# badge.net
KiCad netlist of a schematic drawn in EAGLE
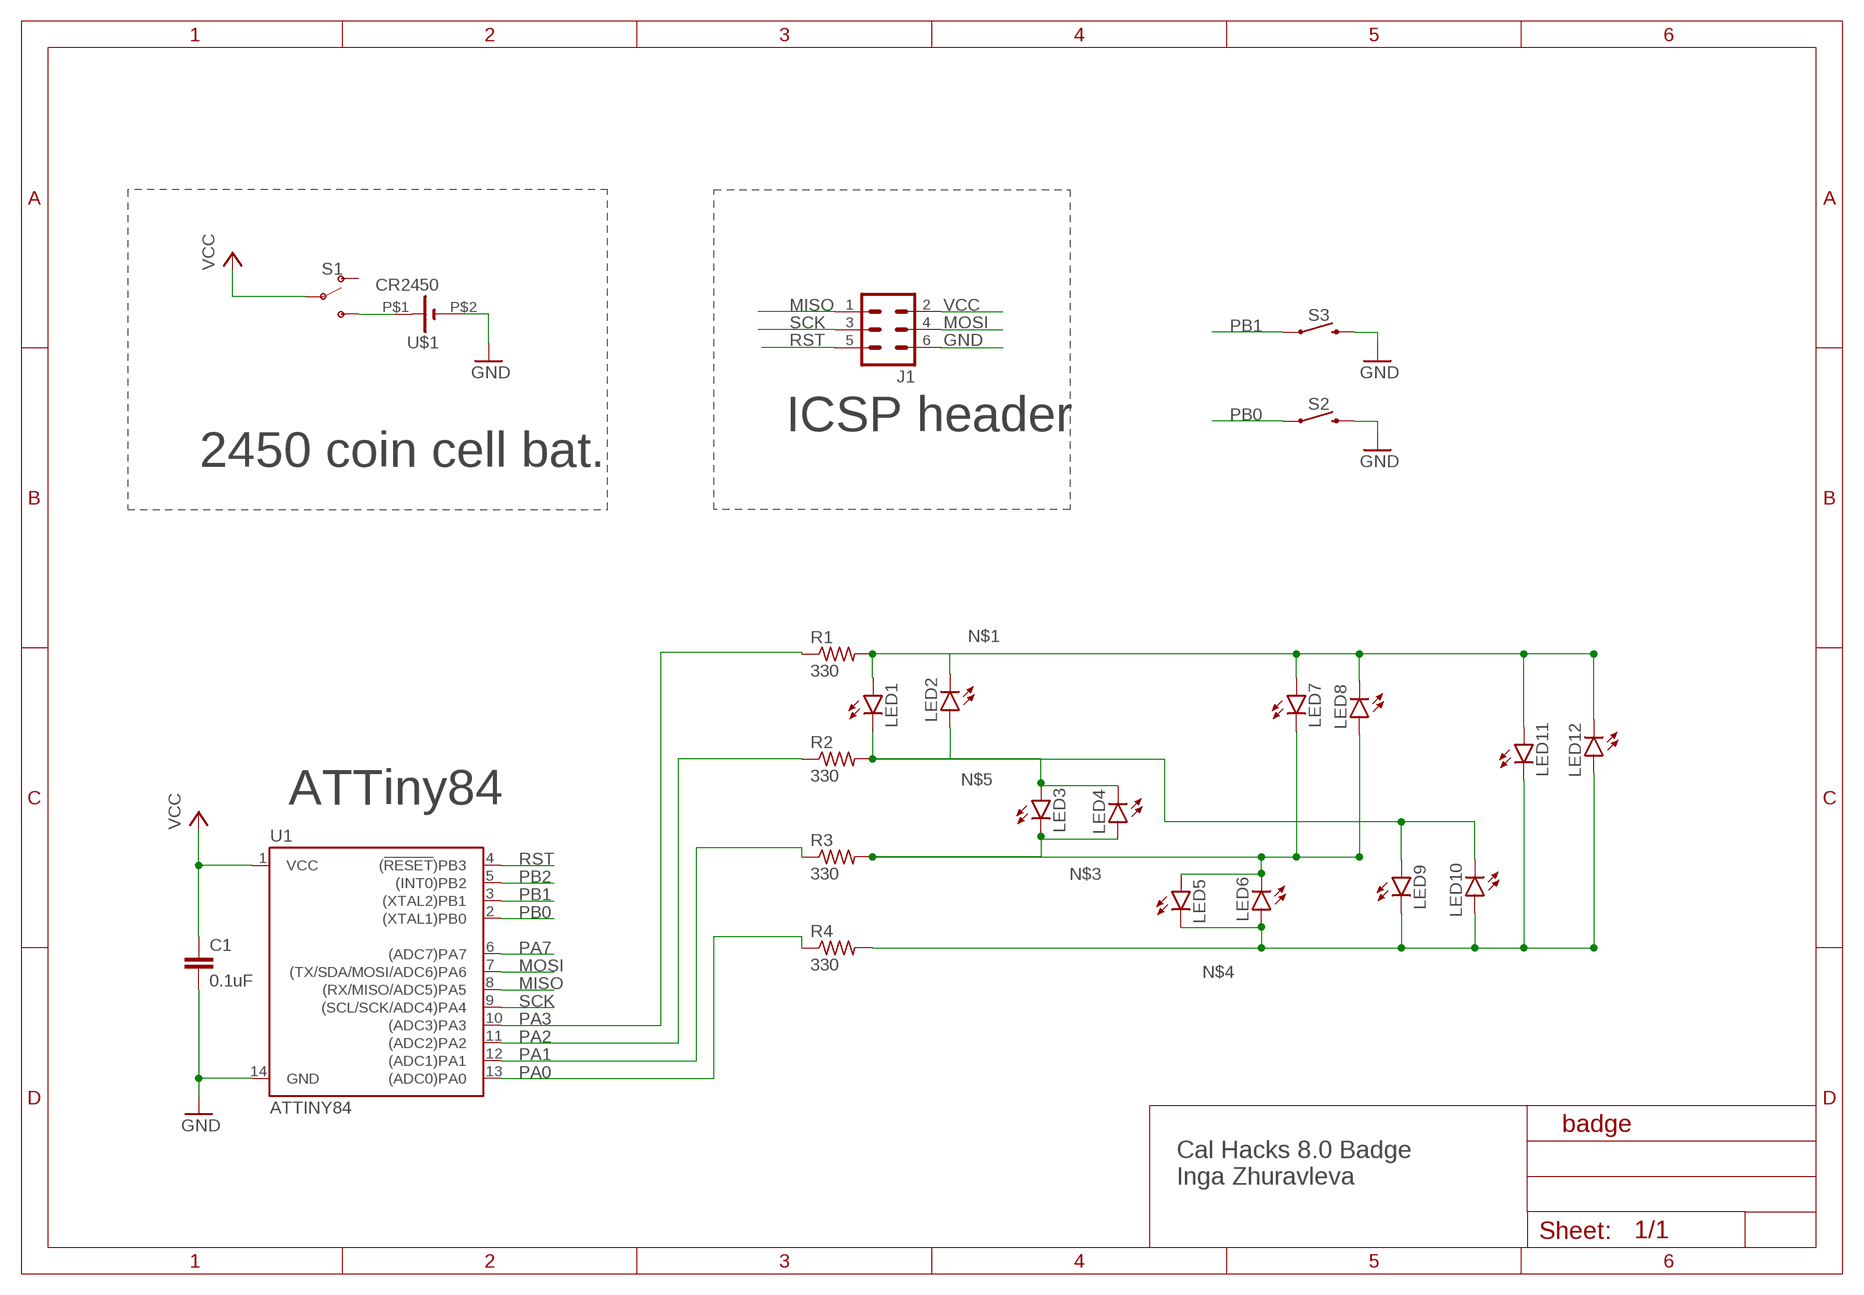
[diagram p0: schematic, sheet 1]

(export (version "E")
  (design (tool "Eeschema 10.0.6"))
  (components
    (comp (ref "C1")
      (value "0.1uF")
      (footprint "eagle-import:C0603")
      (libsource (lib "eagle-import") (part "C-EUC0603"))
    )
    (comp (ref "J1")
      (value "MA03-2")
      (footprint "eagle-import:MA03-2")
      (libsource (lib "eagle-import") (part "MA03-2"))
    )
    (comp (ref "LED1")
      (value "LED3MM")
      (footprint "eagle-import:LED3MM")
      (libsource (lib "eagle-import") (part "LED3MM"))
    )
    (comp (ref "LED2")
      (value "LED3MM")
      (footprint "eagle-import:LED3MM")
      (libsource (lib "eagle-import") (part "LED3MM"))
    )
    (comp (ref "LED3")
      (value "LED3MM")
      (footprint "eagle-import:LED3MM")
      (libsource (lib "eagle-import") (part "LED3MM"))
    )
    (comp (ref "LED4")
      (value "LED3MM")
      (footprint "eagle-import:LED3MM")
      (libsource (lib "eagle-import") (part "LED3MM"))
    )
    (comp (ref "LED5")
      (value "LED3MM")
      (footprint "eagle-import:LED3MM")
      (libsource (lib "eagle-import") (part "LED3MM"))
    )
    (comp (ref "LED6")
      (value "LED3MM")
      (footprint "eagle-import:LED3MM")
      (libsource (lib "eagle-import") (part "LED3MM"))
    )
    (comp (ref "LED7")
      (value "LED3MM")
      (footprint "eagle-import:LED3MM")
      (libsource (lib "eagle-import") (part "LED3MM"))
    )
    (comp (ref "LED8")
      (value "LED3MM")
      (footprint "eagle-import:LED3MM")
      (libsource (lib "eagle-import") (part "LED3MM"))
    )
    (comp (ref "LED9")
      (value "LED3MM")
      (footprint "eagle-import:LED3MM")
      (libsource (lib "eagle-import") (part "LED3MM"))
    )
    (comp (ref "LED10")
      (value "LED3MM")
      (footprint "eagle-import:LED3MM")
      (libsource (lib "eagle-import") (part "LED3MM"))
    )
    (comp (ref "LED11")
      (value "LED3MM")
      (footprint "eagle-import:LED3MM")
      (libsource (lib "eagle-import") (part "LED3MM"))
    )
    (comp (ref "LED12")
      (value "LED3MM")
      (footprint "eagle-import:LED3MM")
      (libsource (lib "eagle-import") (part "LED3MM"))
    )
    (comp (ref "R1")
      (value "330")
      (footprint "eagle-import:R0805")
      (libsource (lib "eagle-import") (part "R-US_R0805"))
    )
    (comp (ref "R2")
      (value "330")
      (footprint "eagle-import:R0805")
      (libsource (lib "eagle-import") (part "R-US_R0805"))
    )
    (comp (ref "R3")
      (value "330")
      (footprint "eagle-import:R0805")
      (libsource (lib "eagle-import") (part "R-US_R0805"))
    )
    (comp (ref "R4")
      (value "330")
      (footprint "eagle-import:R0805")
      (libsource (lib "eagle-import") (part "R-US_R0805"))
    )
    (comp (ref "S1")
      (value "SWITCH-SPDT-PTH-11.6X4.0MM-KIT")
      (footprint "eagle-import:SWITCH_SPDT_PTH_11.6X4.0MM_KIT")
      (libsource (lib "eagle-import") (part "SWITCH-SPDT-PTH-11.6X4.0MM-KIT"))
    )
    (comp (ref "S2")
      (value "MOMENTARY-SWITCH-SPST-SMD-6.2MM-TALL")
      (footprint "eagle-import:TACTILE_SWITCH_SMD_6.2MM_TALL")
      (libsource (lib "eagle-import") (part "MOMENTARY-SWITCH-SPST-SMD-6.2MM-TALL"))
    )
    (comp (ref "S3")
      (value "MOMENTARY-SWITCH-SPST-SMD-6.2MM-TALL")
      (footprint "eagle-import:TACTILE_SWITCH_SMD_6.2MM_TALL")
      (libsource (lib "eagle-import") (part "MOMENTARY-SWITCH-SPST-SMD-6.2MM-TALL"))
    )
    (comp (ref "U$1")
      (value "CR2450")
      (footprint "eagle-import:BAT_2450_XL")
      (fields (field (name "MF") "Murata Electronics"))
      (libsource (lib "eagle-import") (part "CR2450"))
    )
    (comp (ref "U1")
      (value "ATTINY84")
      (footprint "eagle-import:SO14")
      (libsource (lib "eagle-import") (part "ATTINY84"))
    )
  )
  (nets
    (net (code "1") (name "/MISO") (class "Default")
      (node (ref "J1") (pin "1") (pinfunction "1_1") (pintype "passive"))
      (node (ref "U1") (pin "8") (pinfunction "(RX/MISO/ADC5)PA5_8") (pintype "bidirectional"))
    )
    (net (code "2") (name "/MOSI") (class "Default")
      (node (ref "J1") (pin "4") (pinfunction "4_4") (pintype "passive"))
      (node (ref "U1") (pin "7") (pinfunction "(TX/SDA/MOSI/ADC6)PA6_7") (pintype "bidirectional"))
    )
    (net (code "3") (name "/N$1") (class "Default")
      (node (ref "LED1") (pin "A") (pinfunction "A_A") (pintype "passive"))
      (node (ref "LED11") (pin "A") (pinfunction "A_A") (pintype "passive"))
      (node (ref "LED12") (pin "K") (pinfunction "C_K") (pintype "passive"))
      (node (ref "LED2") (pin "K") (pinfunction "C_K") (pintype "passive"))
      (node (ref "LED7") (pin "A") (pinfunction "A_A") (pintype "passive"))
      (node (ref "LED8") (pin "K") (pinfunction "C_K") (pintype "passive"))
      (node (ref "R1") (pin "2") (pinfunction "2_2") (pintype "passive"))
    )
    (net (code "4") (name "/N$3") (class "Default")
      (node (ref "LED3") (pin "K") (pinfunction "C_K") (pintype "passive"))
      (node (ref "LED4") (pin "A") (pinfunction "A_A") (pintype "passive"))
      (node (ref "LED5") (pin "A") (pinfunction "A_A") (pintype "passive"))
      (node (ref "LED6") (pin "K") (pinfunction "C_K") (pintype "passive"))
      (node (ref "LED7") (pin "K") (pinfunction "C_K") (pintype "passive"))
      (node (ref "LED8") (pin "A") (pinfunction "A_A") (pintype "passive"))
      (node (ref "R3") (pin "2") (pinfunction "2_2") (pintype "passive"))
    )
    (net (code "5") (name "/N$4") (class "Default")
      (node (ref "LED10") (pin "A") (pinfunction "A_A") (pintype "passive"))
      (node (ref "LED11") (pin "K") (pinfunction "C_K") (pintype "passive"))
      (node (ref "LED12") (pin "A") (pinfunction "A_A") (pintype "passive"))
      (node (ref "LED5") (pin "K") (pinfunction "C_K") (pintype "passive"))
      (node (ref "LED6") (pin "A") (pinfunction "A_A") (pintype "passive"))
      (node (ref "LED9") (pin "K") (pinfunction "C_K") (pintype "passive"))
      (node (ref "R4") (pin "2") (pinfunction "2_2") (pintype "passive"))
    )
    (net (code "6") (name "/N$5") (class "Default")
      (node (ref "LED1") (pin "K") (pinfunction "C_K") (pintype "passive"))
      (node (ref "LED10") (pin "K") (pinfunction "C_K") (pintype "passive"))
      (node (ref "LED2") (pin "A") (pinfunction "A_A") (pintype "passive"))
      (node (ref "LED3") (pin "A") (pinfunction "A_A") (pintype "passive"))
      (node (ref "LED4") (pin "K") (pinfunction "C_K") (pintype "passive"))
      (node (ref "LED9") (pin "A") (pinfunction "A_A") (pintype "passive"))
      (node (ref "R2") (pin "2") (pinfunction "2_2") (pintype "passive"))
    )
    (net (code "7") (name "/PA0") (class "Default")
      (node (ref "R4") (pin "1") (pinfunction "1_1") (pintype "passive"))
      (node (ref "U1") (pin "13") (pinfunction "(ADC0)PA0_13") (pintype "bidirectional"))
    )
    (net (code "8") (name "/PA1") (class "Default")
      (node (ref "R3") (pin "1") (pinfunction "1_1") (pintype "passive"))
      (node (ref "U1") (pin "12") (pinfunction "(ADC1)PA1_12") (pintype "bidirectional"))
    )
    (net (code "9") (name "/PA2") (class "Default")
      (node (ref "R2") (pin "1") (pinfunction "1_1") (pintype "passive"))
      (node (ref "U1") (pin "11") (pinfunction "(ADC2)PA2_11") (pintype "bidirectional"))
    )
    (net (code "10") (name "/PA3") (class "Default")
      (node (ref "R1") (pin "1") (pinfunction "1_1") (pintype "passive"))
      (node (ref "U1") (pin "10") (pinfunction "(ADC3)PA3_10") (pintype "bidirectional"))
    )
    (net (code "11") (name "/PA7") (class "Default")
      (node (ref "U1") (pin "6") (pinfunction "(ADC7)PA7_6") (pintype "bidirectional"))
    )
    (net (code "12") (name "/PB0") (class "Default")
      (node (ref "S2") (pin "A2") (pinfunction "1_A2") (pintype "passive"))
      (node (ref "U1") (pin "2") (pinfunction "(XTAL1)PB0_2") (pintype "bidirectional"))
    )
    (net (code "13") (name "/PB1") (class "Default")
      (node (ref "S3") (pin "A2") (pinfunction "1_A2") (pintype "passive"))
      (node (ref "U1") (pin "3") (pinfunction "(XTAL2)PB1_3") (pintype "bidirectional"))
    )
    (net (code "14") (name "/PB2") (class "Default")
      (node (ref "U1") (pin "5") (pinfunction "(INT0)PB2_5") (pintype "bidirectional"))
    )
    (net (code "15") (name "/RST") (class "Default")
      (node (ref "J1") (pin "5") (pinfunction "5_5") (pintype "passive"))
      (node (ref "U1") (pin "4") (pinfunction "(~{RESET})PB3_4") (pintype "bidirectional"))
    )
    (net (code "16") (name "/SCK") (class "Default")
      (node (ref "J1") (pin "3") (pinfunction "3_3") (pintype "passive"))
      (node (ref "U1") (pin "9") (pinfunction "(SCL/SCK/ADC4)PA4_9") (pintype "bidirectional"))
    )
    (net (code "17") (name "GND") (class "Default")
      (node (ref "C1") (pin "2") (pinfunction "2_2") (pintype "passive"))
      (node (ref "J1") (pin "6") (pinfunction "6_6") (pintype "passive"))
      (node (ref "S2") (pin "B2") (pinfunction "2_B2") (pintype "passive"))
      (node (ref "S3") (pin "B2") (pinfunction "2_B2") (pintype "passive"))
      (node (ref "U$1") (pin "P$2") (pinfunction "-_P$2") (pintype "passive"))
      (node (ref "U1") (pin "14") (pinfunction "GND_14") (pintype "bidirectional"))
    )
    (net (code "18") (name "Net-(S1-S)") (class "Default")
      (node (ref "S1") (pin "3") (pinfunction "S_3") (pintype "passive"))
      (node (ref "U$1") (pin "P$1") (pinfunction "+_P$1") (pintype "passive"))
    )
    (net (code "19") (name "VCC") (class "Default")
      (node (ref "C1") (pin "1") (pinfunction "1_1") (pintype "passive"))
      (node (ref "J1") (pin "2") (pinfunction "2_2") (pintype "passive"))
      (node (ref "S1") (pin "2") (pinfunction "P_2") (pintype "passive"))
      (node (ref "U1") (pin "1") (pinfunction "VCC_1") (pintype "bidirectional"))
    )
    (net (code "20") (name "unconnected-(S1-O-Pad1)") (class "Default")
      (node (ref "S1") (pin "1") (pinfunction "O_1") (pintype "passive"))
    )
  )
)
